# Attenuverting_VCA.net
KiCad netlist of a schematic drawn in EAGLE
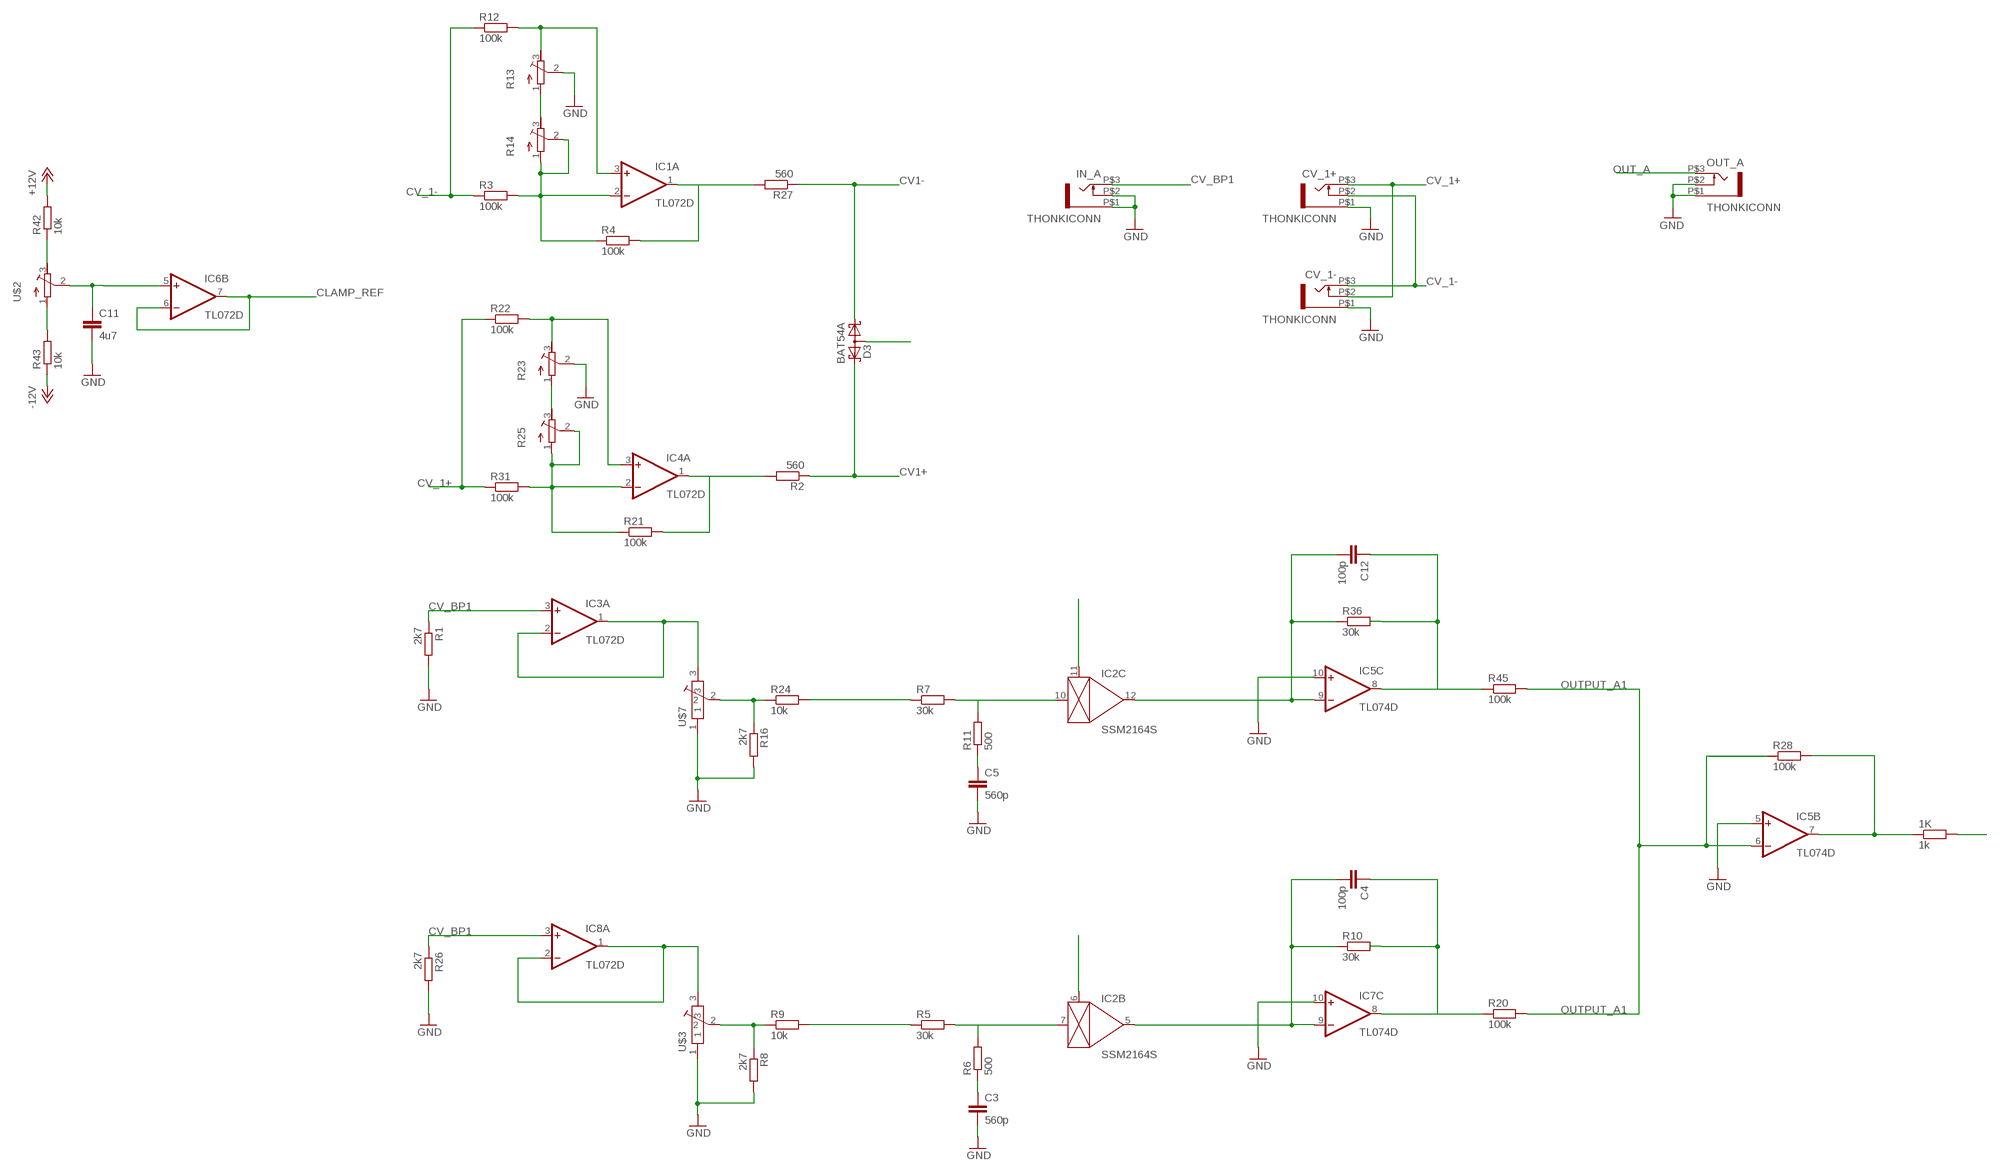
[diagram p0: schematic, sheet 1]

(export (version "E")
  (design (tool "Eeschema 10.0.6"))
  (components
    (comp (ref "1K")
      (value "1k")
      (footprint "eagle-import:0603")
      (libsource (lib "eagle-import") (part "R-EU_0603"))
    )
    (comp (ref "C3")
      (value "560p")
      (footprint "eagle-import:C0603K")
      (libsource (lib "eagle-import") (part "C-EUC0603K"))
    )
    (comp (ref "C4")
      (value "100p")
      (footprint "eagle-import:C0603K")
      (libsource (lib "eagle-import") (part "C-EUC0603K"))
    )
    (comp (ref "C5")
      (value "560p")
      (footprint "eagle-import:C0603K")
      (libsource (lib "eagle-import") (part "C-EUC0603K"))
    )
    (comp (ref "C11")
      (value "4u7")
      (footprint "eagle-import:C0603K")
      (libsource (lib "eagle-import") (part "C-EUC0603K"))
    )
    (comp (ref "C12")
      (value "100p")
      (footprint "eagle-import:C0603K")
      (libsource (lib "eagle-import") (part "C-EUC0603K"))
    )
    (comp (ref "CV_1+")
      (value "THONKICONN")
      (footprint "eagle-import:THONKICONN")
      (libsource (lib "eagle-import") (part "THONKICONN"))
    )
    (comp (ref "CV_1-")
      (value "THONKICONN")
      (footprint "eagle-import:THONKICONN")
      (libsource (lib "eagle-import") (part "THONKICONN"))
    )
    (comp (ref "D3")
      (value "BAT54A")
      (footprint "eagle-import:SOT23")
      (libsource (lib "eagle-import") (part "BAT54A"))
    )
    (comp (ref "IC1")
      (value "TL072D")
      (footprint "eagle-import:SO08")
      (libsource (lib "eagle-import") (part "TL072D"))
    )
    (comp (ref "IC2")
      (value "SSM2164S")
      (footprint "eagle-import:SOIC16N")
      (libsource (lib "eagle-import") (part "SSM2164S"))
    )
    (comp (ref "IC3")
      (value "TL072D")
      (footprint "eagle-import:SO08")
      (libsource (lib "eagle-import") (part "TL072D"))
    )
    (comp (ref "IC4")
      (value "TL072D")
      (footprint "eagle-import:SO08")
      (libsource (lib "eagle-import") (part "TL072D"))
    )
    (comp (ref "IC5")
      (value "TL074D")
      (footprint "eagle-import:SO14")
      (libsource (lib "eagle-import") (part "TL074D"))
    )
    (comp (ref "IC6")
      (value "TL072D")
      (footprint "eagle-import:SO08")
      (libsource (lib "eagle-import") (part "TL072D"))
    )
    (comp (ref "IC7")
      (value "TL074D")
      (footprint "eagle-import:SO14")
      (libsource (lib "eagle-import") (part "TL074D"))
    )
    (comp (ref "IC8")
      (value "TL072D")
      (footprint "eagle-import:SO08")
      (libsource (lib "eagle-import") (part "TL072D"))
    )
    (comp (ref "IN_A")
      (value "THONKICONN")
      (footprint "eagle-import:THONKICONN")
      (libsource (lib "eagle-import") (part "THONKICONN"))
    )
    (comp (ref "OUT_A")
      (value "THONKICONN")
      (footprint "eagle-import:THONKICONN")
      (libsource (lib "eagle-import") (part "THONKICONN"))
    )
    (comp (ref "R1")
      (value "2k7")
      (footprint "eagle-import:0603")
      (libsource (lib "eagle-import") (part "R-EU_0603"))
    )
    (comp (ref "R2")
      (value "560")
      (footprint "eagle-import:0603")
      (libsource (lib "eagle-import") (part "R-EU_0603"))
    )
    (comp (ref "R3")
      (value "100k")
      (footprint "eagle-import:0603")
      (libsource (lib "eagle-import") (part "R-EU_0603"))
    )
    (comp (ref "R4")
      (value "100k")
      (footprint "eagle-import:0603")
      (libsource (lib "eagle-import") (part "R-EU_0603"))
    )
    (comp (ref "R5")
      (value "30k")
      (footprint "eagle-import:0603")
      (libsource (lib "eagle-import") (part "R-EU_0603"))
    )
    (comp (ref "R6")
      (value "500")
      (footprint "eagle-import:0603")
      (libsource (lib "eagle-import") (part "R-EU_0603"))
    )
    (comp (ref "R7")
      (value "30k")
      (footprint "eagle-import:0603")
      (libsource (lib "eagle-import") (part "R-EU_0603"))
    )
    (comp (ref "R8")
      (value "2k7")
      (footprint "eagle-import:0603")
      (libsource (lib "eagle-import") (part "R-EU_0603"))
    )
    (comp (ref "R9")
      (value "10k")
      (footprint "eagle-import:0603")
      (libsource (lib "eagle-import") (part "R-EU_0603"))
    )
    (comp (ref "R10")
      (value "30k")
      (footprint "eagle-import:0603")
      (libsource (lib "eagle-import") (part "R-EU_0603"))
    )
    (comp (ref "R11")
      (value "500")
      (footprint "eagle-import:0603")
      (libsource (lib "eagle-import") (part "R-EU_0603"))
    )
    (comp (ref "R12")
      (value "100k")
      (footprint "eagle-import:0603")
      (libsource (lib "eagle-import") (part "R-EU_0603"))
    )
    (comp (ref "R13")
      (value "R-TRIMM64X")
      (footprint "eagle-import:RTRIM64X")
      (libsource (lib "eagle-import") (part "R-TRIMM64X"))
    )
    (comp (ref "R14")
      (value "R-TRIMM64X")
      (footprint "eagle-import:RTRIM64X")
      (libsource (lib "eagle-import") (part "R-TRIMM64X"))
    )
    (comp (ref "R16")
      (value "2k7")
      (footprint "eagle-import:0603")
      (libsource (lib "eagle-import") (part "R-EU_0603"))
    )
    (comp (ref "R20")
      (value "100k")
      (footprint "eagle-import:0603")
      (libsource (lib "eagle-import") (part "R-EU_0603"))
    )
    (comp (ref "R21")
      (value "100k")
      (footprint "eagle-import:0603")
      (libsource (lib "eagle-import") (part "R-EU_0603"))
    )
    (comp (ref "R22")
      (value "100k")
      (footprint "eagle-import:0603")
      (libsource (lib "eagle-import") (part "R-EU_0603"))
    )
    (comp (ref "R23")
      (value "R-TRIMM64X")
      (footprint "eagle-import:RTRIM64X")
      (libsource (lib "eagle-import") (part "R-TRIMM64X"))
    )
    (comp (ref "R24")
      (value "10k")
      (footprint "eagle-import:0603")
      (libsource (lib "eagle-import") (part "R-EU_0603"))
    )
    (comp (ref "R25")
      (value "R-TRIMM64X")
      (footprint "eagle-import:RTRIM64X")
      (libsource (lib "eagle-import") (part "R-TRIMM64X"))
    )
    (comp (ref "R26")
      (value "2k7")
      (footprint "eagle-import:0603")
      (libsource (lib "eagle-import") (part "R-EU_0603"))
    )
    (comp (ref "R27")
      (value "560")
      (footprint "eagle-import:0603")
      (libsource (lib "eagle-import") (part "R-EU_0603"))
    )
    (comp (ref "R28")
      (value "100k")
      (footprint "eagle-import:0603")
      (libsource (lib "eagle-import") (part "R-EU_0603"))
    )
    (comp (ref "R31")
      (value "100k")
      (footprint "eagle-import:0603")
      (libsource (lib "eagle-import") (part "R-EU_0603"))
    )
    (comp (ref "R36")
      (value "30k")
      (footprint "eagle-import:0603")
      (libsource (lib "eagle-import") (part "R-EU_0603"))
    )
    (comp (ref "R42")
      (value "10k")
      (footprint "eagle-import:0603")
      (libsource (lib "eagle-import") (part "R-EU_0603"))
    )
    (comp (ref "R43")
      (value "10k")
      (footprint "eagle-import:0603")
      (libsource (lib "eagle-import") (part "R-EU_0603"))
    )
    (comp (ref "R45")
      (value "100k")
      (footprint "eagle-import:0603")
      (libsource (lib "eagle-import") (part "R-EU_0603"))
    )
    (comp (ref "U$2")
      (value "R-TRIMM64W")
      (footprint "eagle-import:RTRIM64W")
      (libsource (lib "eagle-import") (part "R-TRIMM64W"))
    )
    (comp (ref "U$3")
      (value "POT-ALPS-RK09L1140")
      (footprint "eagle-import:POT-ALPS-RK09L1140")
      (libsource (lib "eagle-import") (part "POT-ALPS-RK09L1140"))
    )
    (comp (ref "U$7")
      (value "POT-ALPS-RK09L1140")
      (footprint "eagle-import:POT-ALPS-RK09L1140")
      (libsource (lib "eagle-import") (part "POT-ALPS-RK09L1140"))
    )
  )
  (nets
    (net (code "1") (name "+12V") (class "Default")
      (node (ref "R42") (pin "2") (pinfunction "2_2") (pintype "passive"))
    )
    (net (code "2") (name "-12V") (class "Default")
      (node (ref "R43") (pin "1") (pinfunction "1_1") (pintype "passive"))
    )
    (net (code "3") (name "/CLAMP_REF") (class "Default")
      (node (ref "D3") (pin "3") (pinfunction "AA_3") (pintype "passive"))
      (node (ref "IC6") (pin "6") (pinfunction "-IN_6") (pintype "input"))
      (node (ref "IC6") (pin "7") (pinfunction "OUT_7") (pintype "output"))
    )
    (net (code "4") (name "/CV1+") (class "Default")
      (node (ref "D3") (pin "2") (pinfunction "K2_2") (pintype "passive"))
      (node (ref "IC2") (pin "11") (pinfunction "CTRL_11") (pintype "input"))
      (node (ref "R2") (pin "1") (pinfunction "1_1") (pintype "passive"))
    )
    (net (code "5") (name "/CV1-") (class "Default")
      (node (ref "D3") (pin "1") (pinfunction "K1_1") (pintype "passive"))
      (node (ref "IC2") (pin "6") (pinfunction "CTRL_6") (pintype "input"))
      (node (ref "R27") (pin "1") (pinfunction "1_1") (pintype "passive"))
    )
    (net (code "6") (name "/CV_1+") (class "Default")
      (node (ref "CV_1+") (pin "P$3") (pinfunction "3_P$3") (pintype "passive"))
      (node (ref "CV_1-") (pin "P$2") (pinfunction "4_P$2") (pintype "passive"))
      (node (ref "R22") (pin "1") (pinfunction "1_1") (pintype "passive"))
      (node (ref "R31") (pin "1") (pinfunction "1_1") (pintype "passive"))
    )
    (net (code "7") (name "/CV_1-") (class "Default")
      (node (ref "CV_1+") (pin "P$2") (pinfunction "4_P$2") (pintype "passive"))
      (node (ref "CV_1-") (pin "P$3") (pinfunction "3_P$3") (pintype "passive"))
      (node (ref "R12") (pin "1") (pinfunction "1_1") (pintype "passive"))
      (node (ref "R3") (pin "1") (pinfunction "1_1") (pintype "passive"))
    )
    (net (code "8") (name "/CV_BP1") (class "Default")
      (node (ref "IC3") (pin "3") (pinfunction "+IN_3") (pintype "input"))
      (node (ref "IC8") (pin "3") (pinfunction "+IN_3") (pintype "input"))
      (node (ref "IN_A") (pin "P$3") (pinfunction "3_P$3") (pintype "passive"))
      (node (ref "R1") (pin "1") (pinfunction "1_1") (pintype "passive"))
      (node (ref "R26") (pin "1") (pinfunction "1_1") (pintype "passive"))
    )
    (net (code "9") (name "/OUTPUT_A1") (class "Default")
      (node (ref "IC5") (pin "6") (pinfunction "-IN_6") (pintype "input"))
      (node (ref "R20") (pin "2") (pinfunction "2_2") (pintype "passive"))
      (node (ref "R28") (pin "1") (pinfunction "1_1") (pintype "passive"))
      (node (ref "R45") (pin "2") (pinfunction "2_2") (pintype "passive"))
    )
    (net (code "10") (name "/OUT_A") (class "Default")
      (node (ref "OUT_A") (pin "P$3") (pinfunction "3_P$3") (pintype "passive"))
    )
    (net (code "11") (name "GND") (class "Default")
      (node (ref "C11") (pin "2") (pinfunction "2_2") (pintype "passive"))
      (node (ref "C3") (pin "2") (pinfunction "2_2") (pintype "passive"))
      (node (ref "C5") (pin "2") (pinfunction "2_2") (pintype "passive"))
      (node (ref "CV_1+") (pin "P$1") (pinfunction "5_P$1") (pintype "passive"))
      (node (ref "CV_1-") (pin "P$1") (pinfunction "5_P$1") (pintype "passive"))
      (node (ref "IC5") (pin "10") (pinfunction "+IN_10") (pintype "input"))
      (node (ref "IC5") (pin "5") (pinfunction "+IN_5") (pintype "input"))
      (node (ref "IC7") (pin "10") (pinfunction "+IN_10") (pintype "input"))
      (node (ref "IN_A") (pin "P$1") (pinfunction "5_P$1") (pintype "passive"))
      (node (ref "IN_A") (pin "P$2") (pinfunction "4_P$2") (pintype "passive"))
      (node (ref "OUT_A") (pin "P$1") (pinfunction "5_P$1") (pintype "passive"))
      (node (ref "OUT_A") (pin "P$2") (pinfunction "4_P$2") (pintype "passive"))
      (node (ref "R1") (pin "2") (pinfunction "2_2") (pintype "passive"))
      (node (ref "R13") (pin "2") (pinfunction "S_2") (pintype "passive"))
      (node (ref "R16") (pin "2") (pinfunction "2_2") (pintype "passive"))
      (node (ref "R23") (pin "2") (pinfunction "S_2") (pintype "passive"))
      (node (ref "R26") (pin "2") (pinfunction "2_2") (pintype "passive"))
      (node (ref "R8") (pin "2") (pinfunction "2_2") (pintype "passive"))
      (node (ref "U$3") (pin "1") (pinfunction "1_1") (pintype "bidirectional"))
      (node (ref "U$7") (pin "1") (pinfunction "1_1") (pintype "bidirectional"))
    )
    (net (code "12") (name "Net-(C3-Pad1)") (class "Default")
      (node (ref "C3") (pin "1") (pinfunction "1_1") (pintype "passive"))
      (node (ref "R6") (pin "1") (pinfunction "1_1") (pintype "passive"))
    )
    (net (code "13") (name "Net-(C5-Pad1)") (class "Default")
      (node (ref "C5") (pin "1") (pinfunction "1_1") (pintype "passive"))
      (node (ref "R11") (pin "1") (pinfunction "1_1") (pintype "passive"))
    )
    (net (code "14") (name "Net-(IC1A-+IN)") (class "Default")
      (node (ref "IC1") (pin "3") (pinfunction "+IN_3") (pintype "input"))
      (node (ref "R12") (pin "2") (pinfunction "2_2") (pintype "passive"))
      (node (ref "R13") (pin "3") (pinfunction "E_3") (pintype "passive"))
    )
    (net (code "15") (name "Net-(IC1A--IN)") (class "Default")
      (node (ref "IC1") (pin "2") (pinfunction "-IN_2") (pintype "input"))
      (node (ref "R14") (pin "1") (pinfunction "A_1") (pintype "passive"))
      (node (ref "R14") (pin "2") (pinfunction "S_2") (pintype "passive"))
      (node (ref "R3") (pin "2") (pinfunction "2_2") (pintype "passive"))
      (node (ref "R4") (pin "1") (pinfunction "1_1") (pintype "passive"))
    )
    (net (code "16") (name "Net-(IC1A-OUT)") (class "Default")
      (node (ref "IC1") (pin "1") (pinfunction "OUT_1") (pintype "output"))
      (node (ref "R27") (pin "2") (pinfunction "2_2") (pintype "passive"))
      (node (ref "R4") (pin "2") (pinfunction "2_2") (pintype "passive"))
    )
    (net (code "17") (name "Net-(IC2B-IN)") (class "Default")
      (node (ref "IC2") (pin "7") (pinfunction "IN_7") (pintype "input"))
      (node (ref "R5") (pin "2") (pinfunction "2_2") (pintype "passive"))
      (node (ref "R6") (pin "2") (pinfunction "2_2") (pintype "passive"))
    )
    (net (code "18") (name "Net-(IC2B-OUT)") (class "Default")
      (node (ref "C4") (pin "2") (pinfunction "2_2") (pintype "passive"))
      (node (ref "IC2") (pin "5") (pinfunction "OUT_5") (pintype "output"))
      (node (ref "IC7") (pin "9") (pinfunction "-IN_9") (pintype "input"))
      (node (ref "R10") (pin "1") (pinfunction "1_1") (pintype "passive"))
    )
    (net (code "19") (name "Net-(IC2C-IN)") (class "Default")
      (node (ref "IC2") (pin "10") (pinfunction "IN_10") (pintype "input"))
      (node (ref "R11") (pin "2") (pinfunction "2_2") (pintype "passive"))
      (node (ref "R7") (pin "2") (pinfunction "2_2") (pintype "passive"))
    )
    (net (code "20") (name "Net-(IC2C-OUT)") (class "Default")
      (node (ref "C12") (pin "2") (pinfunction "2_2") (pintype "passive"))
      (node (ref "IC2") (pin "12") (pinfunction "OUT_12") (pintype "output"))
      (node (ref "IC5") (pin "9") (pinfunction "-IN_9") (pintype "input"))
      (node (ref "R36") (pin "1") (pinfunction "1_1") (pintype "passive"))
    )
    (net (code "21") (name "Net-(IC3A--IN)") (class "Default")
      (node (ref "IC3") (pin "1") (pinfunction "OUT_1") (pintype "output"))
      (node (ref "IC3") (pin "2") (pinfunction "-IN_2") (pintype "input"))
      (node (ref "U$7") (pin "3") (pinfunction "3_3") (pintype "bidirectional"))
    )
    (net (code "22") (name "Net-(IC4A-+IN)") (class "Default")
      (node (ref "IC4") (pin "3") (pinfunction "+IN_3") (pintype "input"))
      (node (ref "R22") (pin "2") (pinfunction "2_2") (pintype "passive"))
      (node (ref "R23") (pin "3") (pinfunction "E_3") (pintype "passive"))
    )
    (net (code "23") (name "Net-(IC4A--IN)") (class "Default")
      (node (ref "IC4") (pin "2") (pinfunction "-IN_2") (pintype "input"))
      (node (ref "R21") (pin "1") (pinfunction "1_1") (pintype "passive"))
      (node (ref "R25") (pin "1") (pinfunction "A_1") (pintype "passive"))
      (node (ref "R25") (pin "2") (pinfunction "S_2") (pintype "passive"))
      (node (ref "R31") (pin "2") (pinfunction "2_2") (pintype "passive"))
    )
    (net (code "24") (name "Net-(IC4A-OUT)") (class "Default")
      (node (ref "IC4") (pin "1") (pinfunction "OUT_1") (pintype "output"))
      (node (ref "R2") (pin "2") (pinfunction "2_2") (pintype "passive"))
      (node (ref "R21") (pin "2") (pinfunction "2_2") (pintype "passive"))
    )
    (net (code "25") (name "Net-(IC5B-OUT)") (class "Default")
      (node (ref "1K") (pin "1") (pinfunction "1_1") (pintype "passive"))
      (node (ref "IC5") (pin "7") (pinfunction "OUT_7") (pintype "output"))
      (node (ref "R28") (pin "2") (pinfunction "2_2") (pintype "passive"))
    )
    (net (code "26") (name "Net-(IC5C-OUT)") (class "Default")
      (node (ref "C12") (pin "1") (pinfunction "1_1") (pintype "passive"))
      (node (ref "IC5") (pin "8") (pinfunction "OUT_8") (pintype "output"))
      (node (ref "R36") (pin "2") (pinfunction "2_2") (pintype "passive"))
      (node (ref "R45") (pin "1") (pinfunction "1_1") (pintype "passive"))
    )
    (net (code "27") (name "Net-(IC6B-+IN)") (class "Default")
      (node (ref "C11") (pin "1") (pinfunction "1_1") (pintype "passive"))
      (node (ref "IC6") (pin "5") (pinfunction "+IN_5") (pintype "input"))
      (node (ref "U$2") (pin "2") (pinfunction "S_2") (pintype "passive"))
    )
    (net (code "28") (name "Net-(IC7C-OUT)") (class "Default")
      (node (ref "C4") (pin "1") (pinfunction "1_1") (pintype "passive"))
      (node (ref "IC7") (pin "8") (pinfunction "OUT_8") (pintype "output"))
      (node (ref "R10") (pin "2") (pinfunction "2_2") (pintype "passive"))
      (node (ref "R20") (pin "1") (pinfunction "1_1") (pintype "passive"))
    )
    (net (code "29") (name "Net-(IC8A--IN)") (class "Default")
      (node (ref "IC8") (pin "1") (pinfunction "OUT_1") (pintype "output"))
      (node (ref "IC8") (pin "2") (pinfunction "-IN_2") (pintype "input"))
      (node (ref "U$3") (pin "3") (pinfunction "3_3") (pintype "bidirectional"))
    )
    (net (code "30") (name "Net-(R5-Pad1)") (class "Default")
      (node (ref "R5") (pin "1") (pinfunction "1_1") (pintype "passive"))
      (node (ref "R9") (pin "2") (pinfunction "2_2") (pintype "passive"))
    )
    (net (code "31") (name "Net-(R8-Pad1)") (class "Default")
      (node (ref "R8") (pin "1") (pinfunction "1_1") (pintype "passive"))
      (node (ref "R9") (pin "1") (pinfunction "1_1") (pintype "passive"))
      (node (ref "U$3") (pin "2") (pinfunction "2_2") (pintype "bidirectional"))
    )
    (net (code "32") (name "Net-(R13-A)") (class "Default")
      (node (ref "R13") (pin "1") (pinfunction "A_1") (pintype "passive"))
      (node (ref "R14") (pin "3") (pinfunction "E_3") (pintype "passive"))
    )
    (net (code "33") (name "Net-(R16-Pad1)") (class "Default")
      (node (ref "R16") (pin "1") (pinfunction "1_1") (pintype "passive"))
      (node (ref "R24") (pin "1") (pinfunction "1_1") (pintype "passive"))
      (node (ref "U$7") (pin "2") (pinfunction "2_2") (pintype "bidirectional"))
    )
    (net (code "34") (name "Net-(R23-A)") (class "Default")
      (node (ref "R23") (pin "1") (pinfunction "A_1") (pintype "passive"))
      (node (ref "R25") (pin "3") (pinfunction "E_3") (pintype "passive"))
    )
    (net (code "35") (name "Net-(R24-Pad2)") (class "Default")
      (node (ref "R24") (pin "2") (pinfunction "2_2") (pintype "passive"))
      (node (ref "R7") (pin "1") (pinfunction "1_1") (pintype "passive"))
    )
    (net (code "36") (name "Net-(U$2-A)") (class "Default")
      (node (ref "R43") (pin "2") (pinfunction "2_2") (pintype "passive"))
      (node (ref "U$2") (pin "1") (pinfunction "A_1") (pintype "passive"))
    )
    (net (code "37") (name "Net-(U$2-E)") (class "Default")
      (node (ref "R42") (pin "1") (pinfunction "1_1") (pintype "passive"))
      (node (ref "U$2") (pin "3") (pinfunction "E_3") (pintype "passive"))
    )
    (net (code "38") (name "unconnected-(1K-Pad2)") (class "Default")
      (node (ref "1K") (pin "2") (pinfunction "2_2") (pintype "passive"))
    )
  )
)
